# B_Register_Electronic_Scheme_2021-10-06.net
KiCad netlist of a schematic drawn in Altium Designer
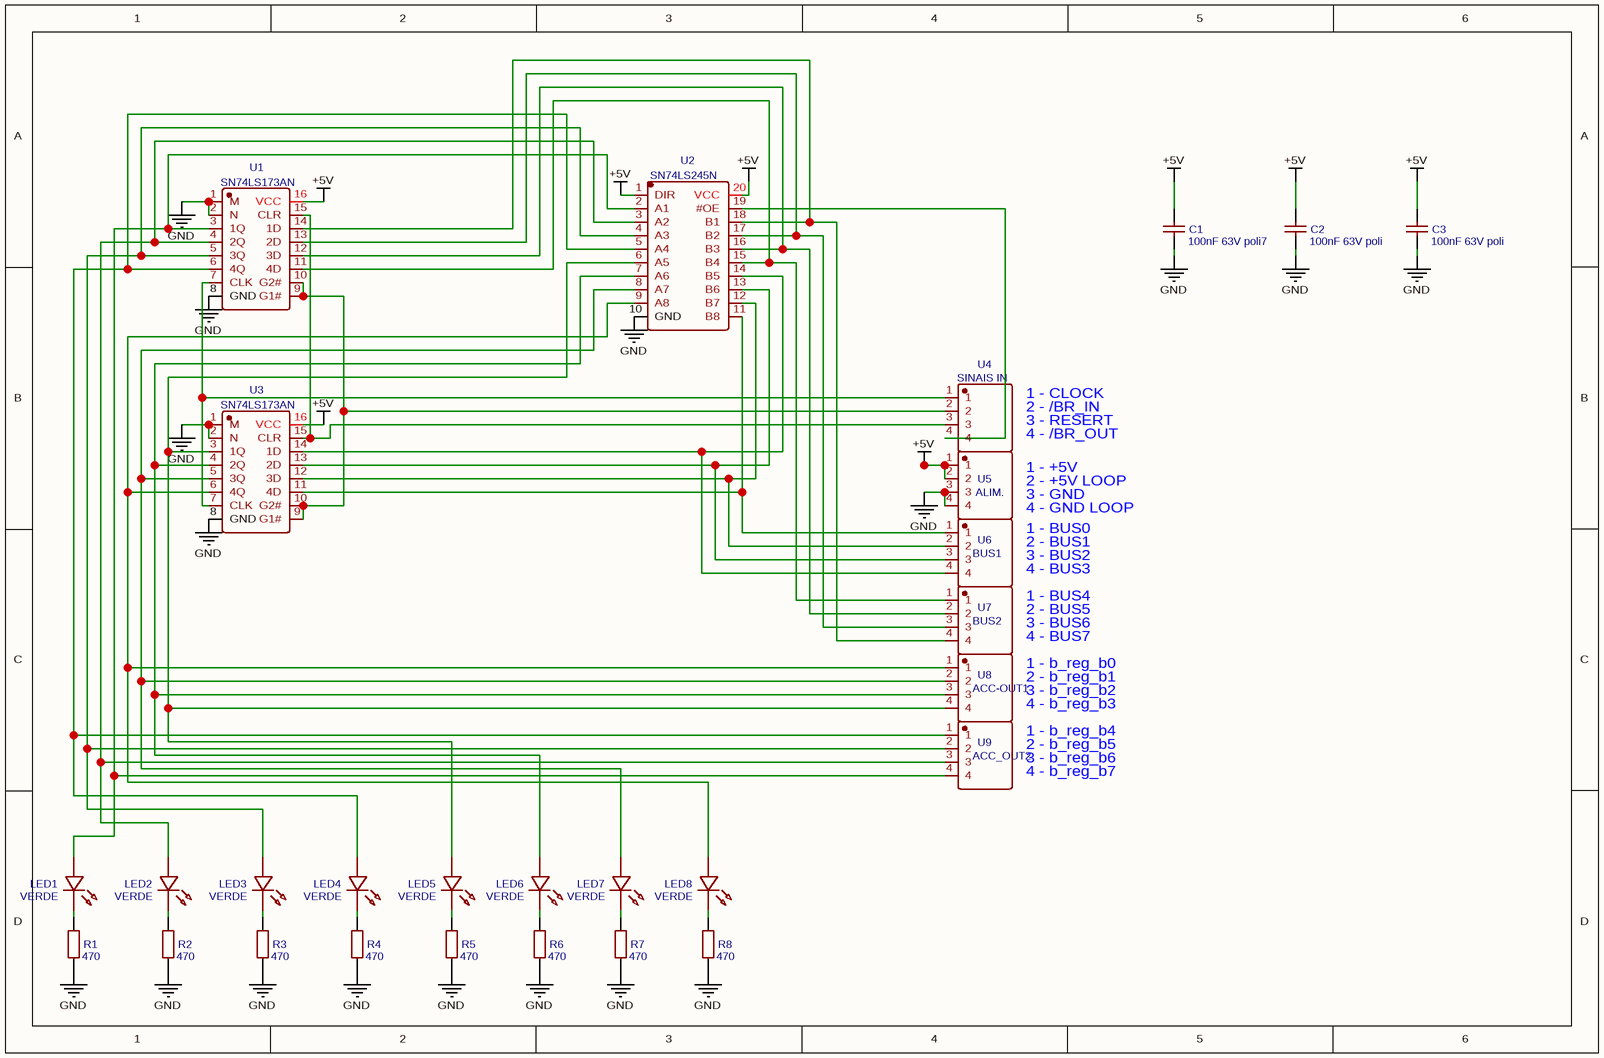
[diagram p0: B Register Electronic Scheme_2021-10-06.schdoc]

(export (version "E")
  (design (tool "Eeschema 10.0.6"))
  (components
    (comp (ref "C1")
      (value "100nF 63V poli7")
      (fields
        (field (name "BOM_SUPPLIER PART") "C444741")
        (field (name "BOM_MANUFACTURER PART") "SR305C105KAR")
        (field (name "CONTRIBUTOR") "LCSC")
      )
      (libsource (lib "altium-import") (part "root_3_100nF 63V poli7_"))
    )
    (comp (ref "C2")
      (value "100nF 63V poli")
      (fields
        (field (name "BOM_SUPPLIER PART") "C444741")
        (field (name "BOM_MANUFACTURER PART") "SR305C105KAR")
        (field (name "CONTRIBUTOR") "LCSC")
      )
      (libsource (lib "altium-import") (part "root_3_100nF 63V poli_"))
    )
    (comp (ref "C3")
      (value "100nF 63V poli")
      (fields
        (field (name "BOM_SUPPLIER PART") "C444741")
        (field (name "BOM_MANUFACTURER PART") "SR305C105KAR")
        (field (name "CONTRIBUTOR") "LCSC")
      )
      (libsource (lib "altium-import") (part "root_3_100nF 63V poli_"))
    )
    (comp (ref "LED1")
      (value "VERDE")
      (fields
        (field (name "BOM_SUPPLIER PART") "C605465")
        (field (name "BOM_MANUFACTURER PART") "264-7GD")
        (field (name "CONTRIBUTOR") "LCSC")
      )
      (libsource (lib "altium-import") (part "root_1_VERDE_"))
    )
    (comp (ref "LED2")
      (value "VERDE")
      (fields
        (field (name "BOM_SUPPLIER PART") "C605465")
        (field (name "BOM_MANUFACTURER PART") "264-7GD")
        (field (name "CONTRIBUTOR") "LCSC")
      )
      (libsource (lib "altium-import") (part "root_1_VERDE_"))
    )
    (comp (ref "LED3")
      (value "VERDE")
      (fields
        (field (name "BOM_SUPPLIER PART") "C605465")
        (field (name "BOM_MANUFACTURER PART") "264-7GD")
        (field (name "CONTRIBUTOR") "LCSC")
      )
      (libsource (lib "altium-import") (part "root_1_VERDE_"))
    )
    (comp (ref "LED4")
      (value "VERDE")
      (fields
        (field (name "BOM_SUPPLIER PART") "C605465")
        (field (name "BOM_MANUFACTURER PART") "264-7GD")
        (field (name "CONTRIBUTOR") "LCSC")
      )
      (libsource (lib "altium-import") (part "root_1_VERDE_"))
    )
    (comp (ref "LED5")
      (value "VERDE")
      (fields
        (field (name "BOM_SUPPLIER PART") "C605465")
        (field (name "BOM_MANUFACTURER PART") "264-7GD")
        (field (name "CONTRIBUTOR") "LCSC")
      )
      (libsource (lib "altium-import") (part "root_1_VERDE_"))
    )
    (comp (ref "LED6")
      (value "VERDE")
      (fields
        (field (name "BOM_SUPPLIER PART") "C605465")
        (field (name "BOM_MANUFACTURER PART") "264-7GD")
        (field (name "CONTRIBUTOR") "LCSC")
      )
      (libsource (lib "altium-import") (part "root_1_VERDE_"))
    )
    (comp (ref "LED7")
      (value "VERDE")
      (fields
        (field (name "BOM_SUPPLIER PART") "C605465")
        (field (name "BOM_MANUFACTURER PART") "264-7GD")
        (field (name "CONTRIBUTOR") "LCSC")
      )
      (libsource (lib "altium-import") (part "root_1_VERDE_"))
    )
    (comp (ref "LED8")
      (value "VERDE")
      (fields
        (field (name "BOM_SUPPLIER PART") "C605465")
        (field (name "BOM_MANUFACTURER PART") "264-7GD")
        (field (name "CONTRIBUTOR") "LCSC")
      )
      (libsource (lib "altium-import") (part "root_1_VERDE_"))
    )
    (comp (ref "R1")
      (value "470")
      (fields
        (field (name "BOM_MANUFACTURER PART") "CFR02SJ0823A10")
        (field (name "BOM_SUPPLIER PART") "C69876")
      )
      (libsource (lib "altium-import") (part "root_3_470_"))
    )
    (comp (ref "R2")
      (value "470")
      (fields
        (field (name "BOM_MANUFACTURER PART") "CFR02SJ0823A10")
        (field (name "BOM_SUPPLIER PART") "C69876")
      )
      (libsource (lib "altium-import") (part "root_3_470_"))
    )
    (comp (ref "R3")
      (value "470")
      (fields
        (field (name "BOM_MANUFACTURER PART") "CFR02SJ0823A10")
        (field (name "BOM_SUPPLIER PART") "C69876")
      )
      (libsource (lib "altium-import") (part "root_3_470_"))
    )
    (comp (ref "R4")
      (value "470")
      (fields
        (field (name "BOM_MANUFACTURER PART") "CFR02SJ0823A10")
        (field (name "BOM_SUPPLIER PART") "C69876")
      )
      (libsource (lib "altium-import") (part "root_3_470_"))
    )
    (comp (ref "R5")
      (value "470")
      (fields
        (field (name "BOM_MANUFACTURER PART") "CFR02SJ0823A10")
        (field (name "BOM_SUPPLIER PART") "C69876")
      )
      (libsource (lib "altium-import") (part "root_3_470_"))
    )
    (comp (ref "R6")
      (value "470")
      (fields
        (field (name "BOM_MANUFACTURER PART") "CFR02SJ0823A10")
        (field (name "BOM_SUPPLIER PART") "C69876")
      )
      (libsource (lib "altium-import") (part "root_3_470_"))
    )
    (comp (ref "R7")
      (value "470")
      (fields
        (field (name "BOM_MANUFACTURER PART") "CFR02SJ0823A10")
        (field (name "BOM_SUPPLIER PART") "C69876")
      )
      (libsource (lib "altium-import") (part "root_3_470_"))
    )
    (comp (ref "R8")
      (value "470")
      (fields
        (field (name "BOM_MANUFACTURER PART") "CFR02SJ0823A10")
        (field (name "BOM_SUPPLIER PART") "C69876")
      )
      (libsource (lib "altium-import") (part "root_3_470_"))
    )
    (comp (ref "U1")
      (value "SN74LS173AN")
      (fields (field (name "BOM_SUPPLIER PART") "C1550125") (field (name "CONTRIBUTOR") "LCSC"))
      (libsource (lib "altium-import") (part "root_0_SN74LS173AN_"))
    )
    (comp (ref "U2")
      (value "SN74LS245N")
      (fields (field (name "BOM_SUPPLIER PART") "C352966") (field (name "CONTRIBUTOR") "LCSC"))
      (libsource (lib "altium-import") (part "root_0_SN74LS245N_"))
    )
    (comp (ref "U3")
      (value "SN74LS173AN")
      (fields (field (name "BOM_SUPPLIER PART") "C1550125") (field (name "CONTRIBUTOR") "LCSC"))
      (libsource (lib "altium-import") (part "root_0_SN74LS173AN_"))
    )
    (comp (ref "U4")
      (value "SINAIS IN")
      (fields
        (field (name "BOM_SUPPLIER PART") "C210162")
        (field (name "BOM_MANUFACTURER PART") "171825-4")
        (field (name "CONTRIBUTOR") "LCSC")
      )
      (libsource (lib "altium-import") (part "root_0_SINAIS IN_"))
    )
    (comp (ref "U5")
      (value "ALIM.")
      (fields
        (field (name "BOM_SUPPLIER PART") "C210162")
        (field (name "BOM_MANUFACTURER PART") "171825-4")
        (field (name "CONTRIBUTOR") "LCSC")
      )
      (libsource (lib "altium-import") (part "root_0_ALIM._"))
    )
    (comp (ref "U6")
      (value "BUS1")
      (fields
        (field (name "BOM_SUPPLIER PART") "C210162")
        (field (name "BOM_MANUFACTURER PART") "171825-4")
        (field (name "CONTRIBUTOR") "LCSC")
      )
      (libsource (lib "altium-import") (part "root_0_BUS1_"))
    )
    (comp (ref "U7")
      (value "BUS2")
      (fields
        (field (name "BOM_SUPPLIER PART") "C210162")
        (field (name "BOM_MANUFACTURER PART") "171825-4")
        (field (name "CONTRIBUTOR") "LCSC")
      )
      (libsource (lib "altium-import") (part "root_0_BUS2_"))
    )
    (comp (ref "U8")
      (value "ACC-OUT1")
      (fields
        (field (name "BOM_SUPPLIER PART") "C210162")
        (field (name "BOM_MANUFACTURER PART") "171825-4")
        (field (name "CONTRIBUTOR") "LCSC")
      )
      (libsource (lib "altium-import") (part "root_0_ACC-OUT1_"))
    )
    (comp (ref "U9")
      (value "ACC_OUT2")
      (fields
        (field (name "BOM_SUPPLIER PART") "C210162")
        (field (name "BOM_MANUFACTURER PART") "171825-4")
        (field (name "CONTRIBUTOR") "LCSC")
      )
      (libsource (lib "altium-import") (part "root_0_ACC_OUT2_"))
    )
  )
  (nets
    (net (code "1") (name "+5V") (class "Default")
      (node (ref "C1") (pin "1") (pinfunction "1_1") (pintype "passive"))
      (node (ref "C2") (pin "1") (pinfunction "1_1") (pintype "passive"))
      (node (ref "C3") (pin "1") (pinfunction "1_1") (pintype "passive"))
      (node (ref "U1") (pin "16") (pinfunction "VCC_16") (pintype "passive"))
      (node (ref "U2") (pin "1") (pinfunction "DIR_1") (pintype "passive"))
      (node (ref "U2") (pin "20") (pinfunction "VCC_20") (pintype "passive"))
      (node (ref "U3") (pin "16") (pinfunction "VCC_16") (pintype "passive"))
      (node (ref "U5") (pin "1") (pinfunction "1_1") (pintype "passive"))
      (node (ref "U5") (pin "2") (pinfunction "2_2") (pintype "passive"))
    )
    (net (code "2") (name "GND") (class "Default")
      (node (ref "C1") (pin "2") (pinfunction "2_2") (pintype "passive"))
      (node (ref "C2") (pin "2") (pinfunction "2_2") (pintype "passive"))
      (node (ref "C3") (pin "2") (pinfunction "2_2") (pintype "passive"))
      (node (ref "R1") (pin "2") (pinfunction "2_2") (pintype "passive"))
      (node (ref "R2") (pin "2") (pinfunction "2_2") (pintype "passive"))
      (node (ref "R3") (pin "2") (pinfunction "2_2") (pintype "passive"))
      (node (ref "R4") (pin "2") (pinfunction "2_2") (pintype "passive"))
      (node (ref "R5") (pin "2") (pinfunction "2_2") (pintype "passive"))
      (node (ref "R6") (pin "2") (pinfunction "2_2") (pintype "passive"))
      (node (ref "R7") (pin "2") (pinfunction "2_2") (pintype "passive"))
      (node (ref "R8") (pin "2") (pinfunction "2_2") (pintype "passive"))
      (node (ref "U1") (pin "1") (pinfunction "M_1") (pintype "passive"))
      (node (ref "U1") (pin "2") (pinfunction "N_2") (pintype "passive"))
      (node (ref "U1") (pin "8") (pinfunction "GND_8") (pintype "passive"))
      (node (ref "U2") (pin "10") (pinfunction "GND_10") (pintype "passive"))
      (node (ref "U3") (pin "1") (pinfunction "M_1") (pintype "passive"))
      (node (ref "U3") (pin "2") (pinfunction "N_2") (pintype "passive"))
      (node (ref "U3") (pin "8") (pinfunction "GND_8") (pintype "passive"))
      (node (ref "U5") (pin "3") (pinfunction "3_3") (pintype "passive"))
      (node (ref "U5") (pin "4") (pinfunction "4_4") (pintype "passive"))
    )
    (net (code "3") (name "Net-(LED1-+)") (class "Default")
      (node (ref "LED1") (pin "2") (pinfunction "+_2") (pintype "passive"))
      (node (ref "U1") (pin "3") (pinfunction "1Q_3") (pintype "passive"))
      (node (ref "U2") (pin "2") (pinfunction "A1_2") (pintype "passive"))
      (node (ref "U9") (pin "4") (pinfunction "4_4") (pintype "passive"))
    )
    (net (code "4") (name "Net-(LED1--)") (class "Default")
      (node (ref "LED1") (pin "1") (pinfunction "-_1") (pintype "passive"))
      (node (ref "R1") (pin "1") (pinfunction "1_1") (pintype "passive"))
    )
    (net (code "5") (name "Net-(LED2-+)") (class "Default")
      (node (ref "LED2") (pin "2") (pinfunction "+_2") (pintype "passive"))
      (node (ref "U1") (pin "4") (pinfunction "2Q_4") (pintype "passive"))
      (node (ref "U2") (pin "3") (pinfunction "A2_3") (pintype "passive"))
      (node (ref "U9") (pin "3") (pinfunction "3_3") (pintype "passive"))
    )
    (net (code "6") (name "Net-(LED2--)") (class "Default")
      (node (ref "LED2") (pin "1") (pinfunction "-_1") (pintype "passive"))
      (node (ref "R2") (pin "1") (pinfunction "1_1") (pintype "passive"))
    )
    (net (code "7") (name "Net-(LED3-+)") (class "Default")
      (node (ref "LED3") (pin "2") (pinfunction "+_2") (pintype "passive"))
      (node (ref "U1") (pin "5") (pinfunction "3Q_5") (pintype "passive"))
      (node (ref "U2") (pin "4") (pinfunction "A3_4") (pintype "passive"))
      (node (ref "U9") (pin "2") (pinfunction "2_2") (pintype "passive"))
    )
    (net (code "8") (name "Net-(LED3--)") (class "Default")
      (node (ref "LED3") (pin "1") (pinfunction "-_1") (pintype "passive"))
      (node (ref "R3") (pin "1") (pinfunction "1_1") (pintype "passive"))
    )
    (net (code "9") (name "Net-(LED4-+)") (class "Default")
      (node (ref "LED4") (pin "2") (pinfunction "+_2") (pintype "passive"))
      (node (ref "U1") (pin "6") (pinfunction "4Q_6") (pintype "passive"))
      (node (ref "U2") (pin "5") (pinfunction "A4_5") (pintype "passive"))
      (node (ref "U9") (pin "1") (pinfunction "1_1") (pintype "passive"))
    )
    (net (code "10") (name "Net-(LED4--)") (class "Default")
      (node (ref "LED4") (pin "1") (pinfunction "-_1") (pintype "passive"))
      (node (ref "R4") (pin "1") (pinfunction "1_1") (pintype "passive"))
    )
    (net (code "11") (name "Net-(LED5-+)") (class "Default")
      (node (ref "LED5") (pin "2") (pinfunction "+_2") (pintype "passive"))
      (node (ref "U2") (pin "6") (pinfunction "A5_6") (pintype "passive"))
      (node (ref "U3") (pin "3") (pinfunction "1Q_3") (pintype "passive"))
      (node (ref "U8") (pin "4") (pinfunction "4_4") (pintype "passive"))
    )
    (net (code "12") (name "Net-(LED5--)") (class "Default")
      (node (ref "LED5") (pin "1") (pinfunction "-_1") (pintype "passive"))
      (node (ref "R5") (pin "1") (pinfunction "1_1") (pintype "passive"))
    )
    (net (code "13") (name "Net-(LED6-+)") (class "Default")
      (node (ref "LED6") (pin "2") (pinfunction "+_2") (pintype "passive"))
      (node (ref "U2") (pin "7") (pinfunction "A6_7") (pintype "passive"))
      (node (ref "U3") (pin "4") (pinfunction "2Q_4") (pintype "passive"))
      (node (ref "U8") (pin "3") (pinfunction "3_3") (pintype "passive"))
    )
    (net (code "14") (name "Net-(LED6--)") (class "Default")
      (node (ref "LED6") (pin "1") (pinfunction "-_1") (pintype "passive"))
      (node (ref "R6") (pin "1") (pinfunction "1_1") (pintype "passive"))
    )
    (net (code "15") (name "Net-(LED7-+)") (class "Default")
      (node (ref "LED7") (pin "2") (pinfunction "+_2") (pintype "passive"))
      (node (ref "U2") (pin "8") (pinfunction "A7_8") (pintype "passive"))
      (node (ref "U3") (pin "5") (pinfunction "3Q_5") (pintype "passive"))
      (node (ref "U8") (pin "2") (pinfunction "2_2") (pintype "passive"))
    )
    (net (code "16") (name "Net-(LED7--)") (class "Default")
      (node (ref "LED7") (pin "1") (pinfunction "-_1") (pintype "passive"))
      (node (ref "R7") (pin "1") (pinfunction "1_1") (pintype "passive"))
    )
    (net (code "17") (name "Net-(LED8-+)") (class "Default")
      (node (ref "LED8") (pin "2") (pinfunction "+_2") (pintype "passive"))
      (node (ref "U2") (pin "9") (pinfunction "A8_9") (pintype "passive"))
      (node (ref "U3") (pin "6") (pinfunction "4Q_6") (pintype "passive"))
      (node (ref "U8") (pin "1") (pinfunction "1_1") (pintype "passive"))
    )
    (net (code "18") (name "Net-(LED8--)") (class "Default")
      (node (ref "LED8") (pin "1") (pinfunction "-_1") (pintype "passive"))
      (node (ref "R8") (pin "1") (pinfunction "1_1") (pintype "passive"))
    )
    (net (code "19") (name "Net-(U1-1D)") (class "Default")
      (node (ref "U1") (pin "14") (pinfunction "1D_14") (pintype "passive"))
      (node (ref "U2") (pin "18") (pinfunction "B1_18") (pintype "passive"))
      (node (ref "U7") (pin "4") (pinfunction "4_4") (pintype "passive"))
    )
    (net (code "20") (name "Net-(U1-2D)") (class "Default")
      (node (ref "U1") (pin "13") (pinfunction "2D_13") (pintype "passive"))
      (node (ref "U2") (pin "17") (pinfunction "B2_17") (pintype "passive"))
      (node (ref "U7") (pin "3") (pinfunction "3_3") (pintype "passive"))
    )
    (net (code "21") (name "Net-(U1-3D)") (class "Default")
      (node (ref "U1") (pin "12") (pinfunction "3D_12") (pintype "passive"))
      (node (ref "U2") (pin "16") (pinfunction "B3_16") (pintype "passive"))
      (node (ref "U7") (pin "2") (pinfunction "2_2") (pintype "passive"))
    )
    (net (code "22") (name "Net-(U1-4D)") (class "Default")
      (node (ref "U1") (pin "11") (pinfunction "4D_11") (pintype "passive"))
      (node (ref "U2") (pin "15") (pinfunction "B4_15") (pintype "passive"))
      (node (ref "U7") (pin "1") (pinfunction "1_1") (pintype "passive"))
    )
    (net (code "23") (name "Net-(U1-CLK)") (class "Default")
      (node (ref "U1") (pin "7") (pinfunction "CLK_7") (pintype "passive"))
      (node (ref "U3") (pin "7") (pinfunction "CLK_7") (pintype "passive"))
      (node (ref "U4") (pin "1") (pinfunction "1_1") (pintype "passive"))
    )
    (net (code "24") (name "Net-(U1-CLR)") (class "Default")
      (node (ref "U1") (pin "15") (pinfunction "CLR_15") (pintype "passive"))
      (node (ref "U3") (pin "15") (pinfunction "CLR_15") (pintype "passive"))
      (node (ref "U4") (pin "3") (pinfunction "3_3") (pintype "passive"))
    )
    (net (code "25") (name "Net-(U1-G1#)") (class "Default")
      (node (ref "U1") (pin "10") (pinfunction "G2#_10") (pintype "passive"))
      (node (ref "U1") (pin "9") (pinfunction "G1#_9") (pintype "passive"))
      (node (ref "U3") (pin "10") (pinfunction "G2#_10") (pintype "passive"))
      (node (ref "U3") (pin "9") (pinfunction "G1#_9") (pintype "passive"))
      (node (ref "U4") (pin "2") (pinfunction "2_2") (pintype "passive"))
    )
    (net (code "26") (name "Net-(U2-#OE)") (class "Default")
      (node (ref "U2") (pin "19") (pinfunction "#OE_19") (pintype "passive"))
      (node (ref "U4") (pin "4") (pinfunction "4_4") (pintype "passive"))
    )
    (net (code "27") (name "Net-(U2-B5)") (class "Default")
      (node (ref "U2") (pin "14") (pinfunction "B5_14") (pintype "passive"))
      (node (ref "U3") (pin "14") (pinfunction "1D_14") (pintype "passive"))
      (node (ref "U6") (pin "4") (pinfunction "4_4") (pintype "passive"))
    )
    (net (code "28") (name "Net-(U2-B6)") (class "Default")
      (node (ref "U2") (pin "13") (pinfunction "B6_13") (pintype "passive"))
      (node (ref "U3") (pin "13") (pinfunction "2D_13") (pintype "passive"))
      (node (ref "U6") (pin "3") (pinfunction "3_3") (pintype "passive"))
    )
    (net (code "29") (name "Net-(U2-B7)") (class "Default")
      (node (ref "U2") (pin "12") (pinfunction "B7_12") (pintype "passive"))
      (node (ref "U3") (pin "12") (pinfunction "3D_12") (pintype "passive"))
      (node (ref "U6") (pin "2") (pinfunction "2_2") (pintype "passive"))
    )
    (net (code "30") (name "Net-(U2-B8)") (class "Default")
      (node (ref "U2") (pin "11") (pinfunction "B8_11") (pintype "passive"))
      (node (ref "U3") (pin "11") (pinfunction "4D_11") (pintype "passive"))
      (node (ref "U6") (pin "1") (pinfunction "1_1") (pintype "passive"))
    )
  )
)
